# schema1.net
KiCad netlist of a schematic drawn in Altium Designer
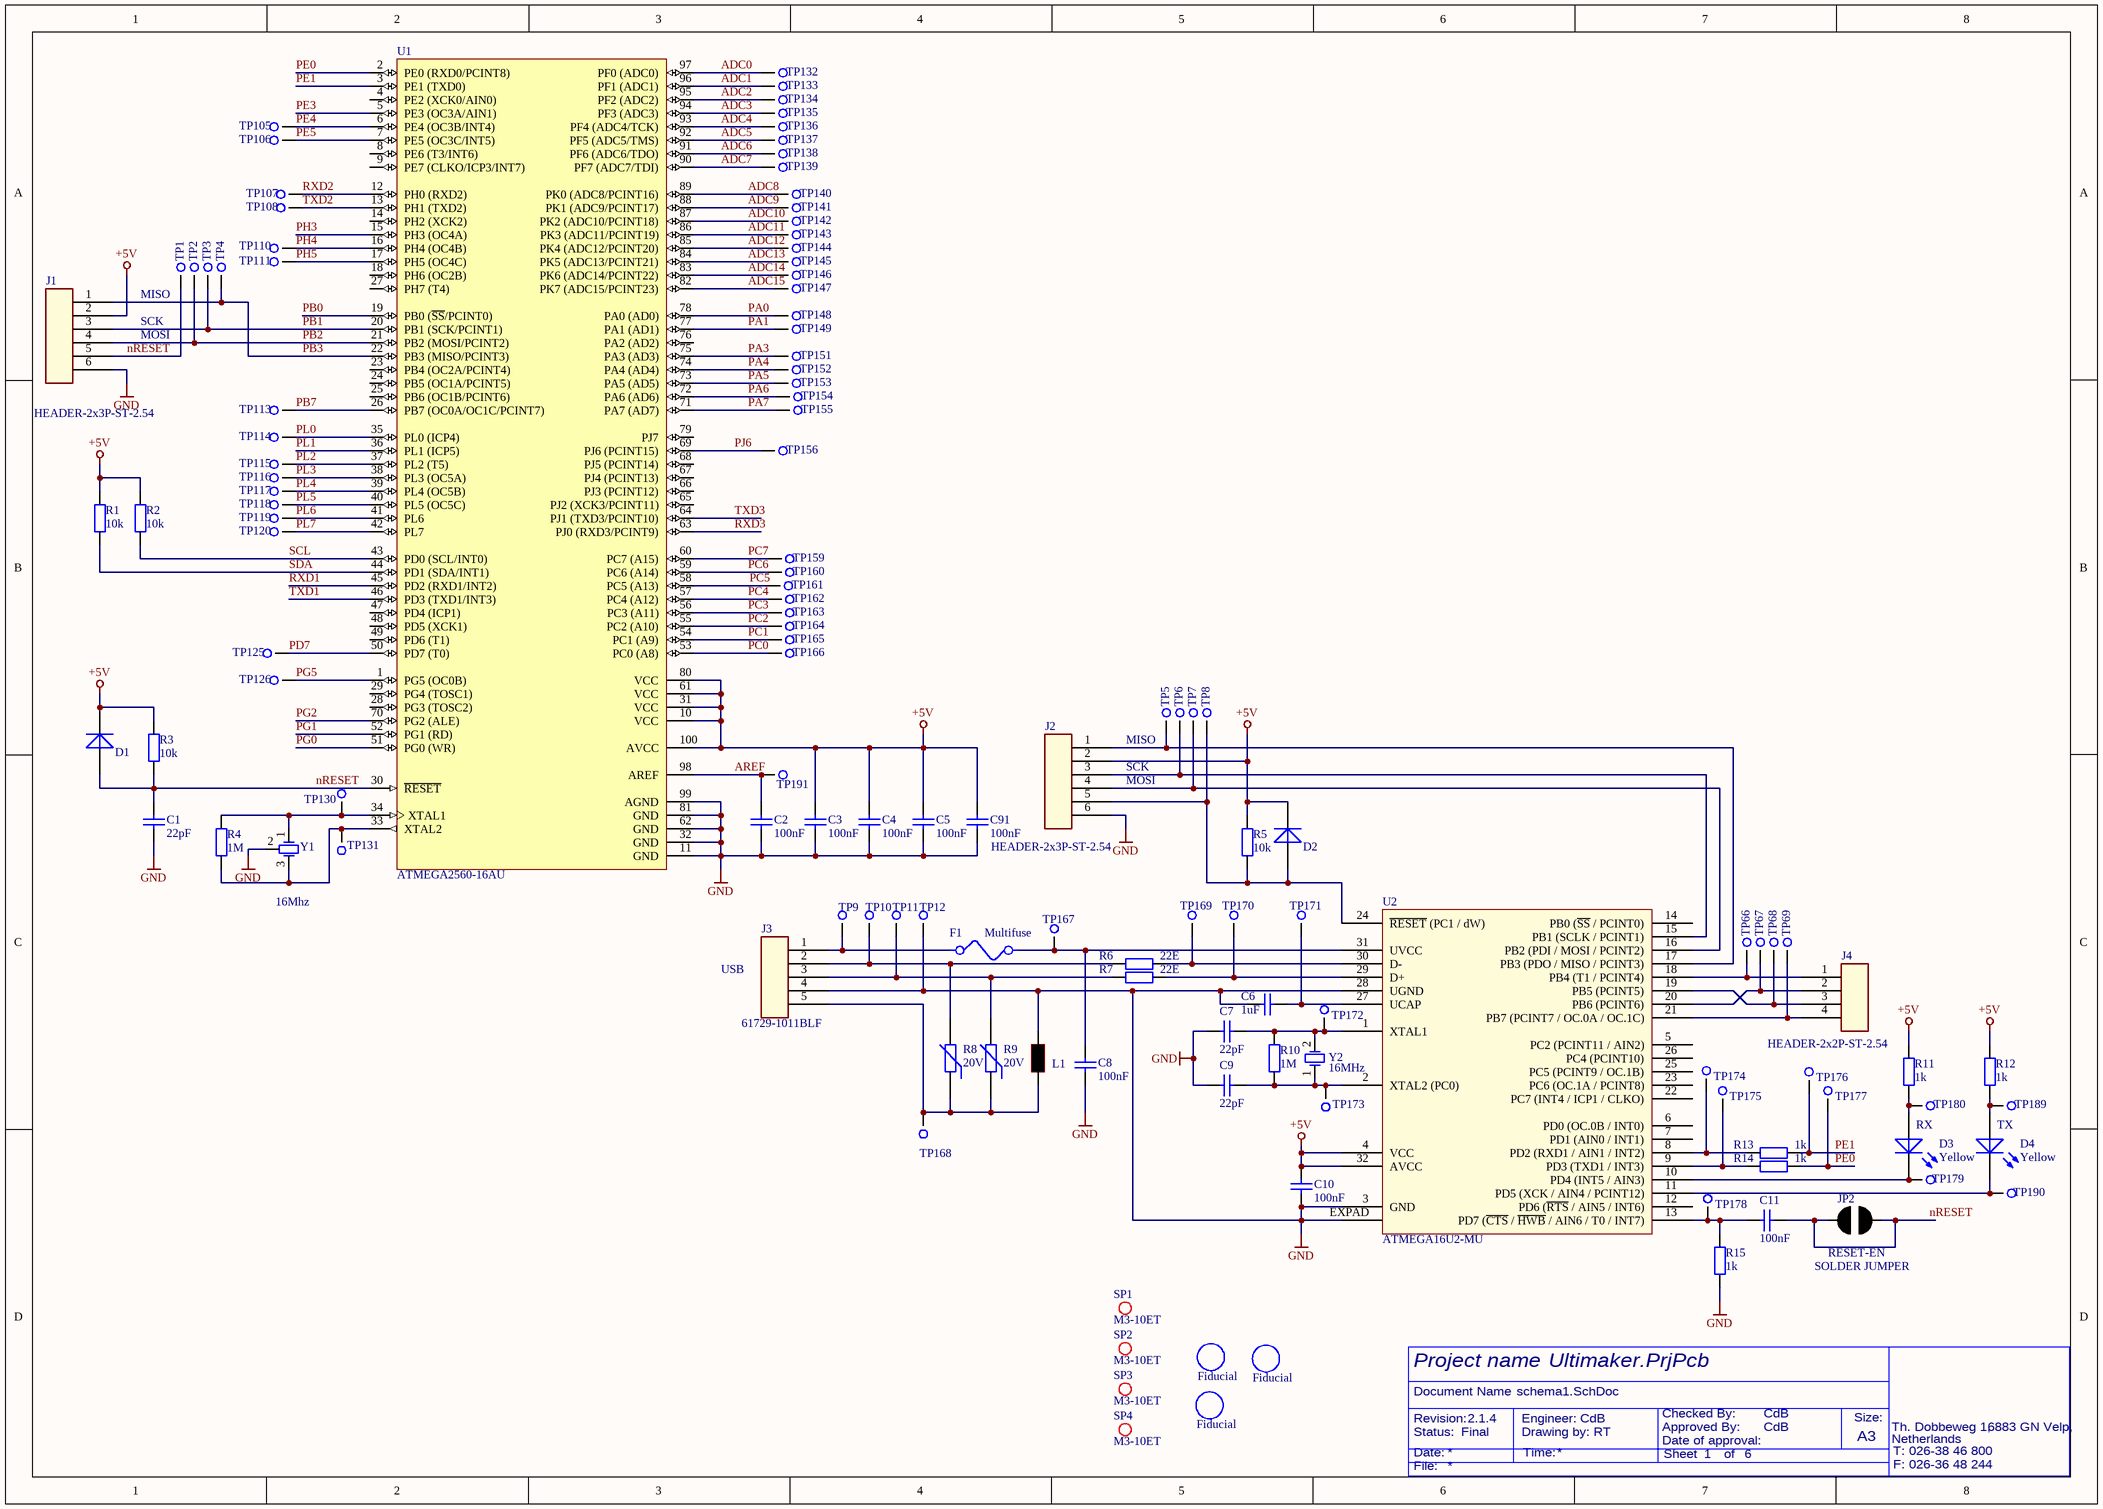
[diagram p0: schema1.SchDoc]

(export (version "E")
  (design (tool "Eeschema 10.0.6"))
  (components
    (comp (ref "C1")
      (value "22pF")
      (footprint "C0603")
      (description "RO C0G 22pF 2% 50V  0603")
      (libsource (lib "Database_Faber") (part "Capacitor"))
    )
    (comp (ref "C2")
      (value "100nF")
      (footprint "C0603")
      (description "RO X7R 100nF 10% 50V 0603")
      (libsource (lib "Database_Faber") (part "Capacitor"))
    )
    (comp (ref "C3")
      (value "100nF")
      (footprint "C0603")
      (description "RO X7R 100nF 10% 50V 0603")
      (libsource (lib "Database_Faber") (part "Capacitor"))
    )
    (comp (ref "C4")
      (value "100nF")
      (footprint "C0603")
      (description "RO X7R 100nF 10% 50V 0603")
      (libsource (lib "Database_Faber") (part "Capacitor"))
    )
    (comp (ref "C5")
      (value "100nF")
      (footprint "C0603")
      (description "RO X7R 100nF 10% 50V 0603")
      (libsource (lib "Database_Faber") (part "Capacitor"))
    )
    (comp (ref "C6")
      (value "1uF")
      (footprint "C0603")
      (description "RO X5R 1uF 10% 10V 0603")
      (libsource (lib "Database_Faber") (part "Capacitor"))
    )
    (comp (ref "C7")
      (value "22pF")
      (footprint "C0603")
      (description "RO C0G 22pF 2% 50V  0603")
      (libsource (lib "Database_Faber") (part "Capacitor"))
    )
    (comp (ref "C8")
      (value "100nF")
      (footprint "C0603")
      (description "RO X7R 100nF 10% 50V 0603")
      (libsource (lib "Database_Faber") (part "Capacitor"))
    )
    (comp (ref "C9")
      (value "22pF")
      (footprint "C0603")
      (description "RO C0G 22pF 2% 50V  0603")
      (libsource (lib "Database_Faber") (part "Capacitor"))
    )
    (comp (ref "C10")
      (value "100nF")
      (footprint "C0603")
      (description "RO X7R 100nF 10% 50V 0603")
      (libsource (lib "Database_Faber") (part "Capacitor"))
    )
    (comp (ref "C11")
      (value "100nF")
      (footprint "C0603")
      (description "RO X7R 100nF 10% 50V 0603")
      (libsource (lib "Database_Faber") (part "Capacitor"))
    )
    (comp (ref "C91")
      (value "100nF")
      (footprint "C0603")
      (description "RO X7R 100nF 10% 50V 0603")
      (libsource (lib "Database_Faber") (part "Capacitor"))
    )
    (comp (ref "D1")
      (value "1N4148")
      (footprint "SOD323")
      (description "RO DIODE 1N4148WS-V-GS08 SOT-323  VISHAY")
      (fields (field (name "MFG") "VISHAY"))
      (libsource (lib "Database_Faber") (part "Diode"))
    )
    (comp (ref "D2")
      (value "1N4148")
      (footprint "SOD323")
      (description "RO DIODE 1N4148WS-V-GS08 SOT-323  VISHAY")
      (fields (field (name "MFG") "VISHAY"))
      (libsource (lib "Database_Faber") (part "Diode"))
    )
    (comp (ref "D3")
      (value "Yellow")
      (footprint "LED0805-YELLOW")
      (description "RO LED GEEL HSMY-C170 0805  AVAGO")
      (fields (field (name "MFG") "AVAGO"))
      (libsource (lib "Database_Faber") (part "LED"))
    )
    (comp (ref "D4")
      (value "Yellow")
      (footprint "LED0805-YELLOW")
      (description "RO LED GEEL HSMY-C170 0805  AVAGO")
      (fields (field (name "MFG") "AVAGO"))
      (libsource (lib "Database_Faber") (part "LED"))
    )
    (comp (ref "F1")
      (value "Multifuse")
      (footprint "Multifuse1812")
      (description "RO ZEK MULTI 500MA SMD 1812 MF-MSMF050-2 BOURNS")
      (fields (field (name "MFG") "BOURNS"))
      (libsource (lib "Database_Faber") (part "Multifuse"))
    )
    (comp (ref "Fid1")
      (value "Fiducial")
      (footprint "Fiducial")
      (libsource (lib "Database_Faber") (part "Fiducial"))
    )
    (comp (ref "Fid2")
      (value "Fiducial")
      (footprint "Fiducial")
      (libsource (lib "Database_Faber") (part "Fiducial"))
    )
    (comp (ref "Fid3")
      (value "Fiducial")
      (footprint "Fiducial")
      (libsource (lib "Database_Faber") (part "Fiducial"))
    )
    (comp (ref "J1")
      (value "HEADER-2x3P-ST-2.54")
      (footprint "HEADER-2x3P-ST-2.54")
      (description "RO CONN PR HDR 2X3P H4B-06DS-0000 INT")
      (libsource (lib "Database_Faber") (part "HEADER 6"))
    )
    (comp (ref "J2")
      (value "HEADER-2x3P-ST-2.54")
      (footprint "HEADER-2x3P-ST-2.54")
      (description "RO CONN PR HDR 2X3P H4B-06DS-0000 INT")
      (libsource (lib "Database_Faber") (part "HEADER 6"))
    )
    (comp (ref "J3")
      (value "61729-1011BLF")
      (footprint "61729-1011BLF")
      (description "RO CONN PR USB-B HKS 61729-1011BLF FCI")
      (fields (field (name "MFG") "FCI"))
      (libsource (lib "Database_Faber") (part "HEADER 5"))
    )
    (comp (ref "J4")
      (value "HEADER-2x2P-ST-2.54")
      (footprint "HEADER-2x2P-ST-2.54")
      (description "HDR 2X2P")
      (libsource (lib "Database_Faber") (part "HEADER 4"))
    )
    (comp (ref "JP2")
      (value "SOLDER JUMPER")
      (footprint "JUMPER 2 SOLDER")
      (libsource (lib "Database_Faber") (part "JUMPER 2 SOLDER"))
    )
    (comp (ref "L1")
      (value "Bead")
      (footprint "L0805")
      (description "RO FERRIET BLM21PG221SN1D  0805")
      (libsource (lib "Database_Faber") (part "Bead"))
    )
    (comp (ref "R1")
      (value "10k")
      (footprint "R0603")
      (description "RO RES 10k0 1% 0,063W  0603")
      (libsource (lib "") (part "Resistor_2"))
    )
    (comp (ref "R2")
      (value "10k")
      (footprint "R0603")
      (description "RO RES 10k0 1% 0,063W  0603")
      (libsource (lib "") (part "Resistor_2"))
    )
    (comp (ref "R3")
      (value "10k")
      (footprint "R0603")
      (description "RO RES 10k0 1% 0,063W  0603")
      (libsource (lib "") (part "Resistor_1"))
    )
    (comp (ref "R4")
      (value "1M")
      (footprint "R0603")
      (description "RO RES 1M0 1% 0,1W 0603")
      (libsource (lib "") (part "Resistor_1"))
    )
    (comp (ref "R5")
      (value "10k")
      (footprint "R0603")
      (description "RO RES 10k0 1% 0,063W  0603")
      (libsource (lib "") (part "Resistor_2"))
    )
    (comp (ref "R6")
      (value "22E")
      (footprint "R0603")
      (description "RO RES 22E0 1% 0,063W 0603")
      (libsource (lib "Database_Faber") (part "Resistor"))
    )
    (comp (ref "R7")
      (value "22E")
      (footprint "R0603")
      (description "RO RES 22E0 1% 0,063W 0603")
      (libsource (lib "Database_Faber") (part "Resistor"))
    )
    (comp (ref "R8")
      (value "20V")
      (footprint "R0603")
      (description "RO VDR 0603 CG0603MLC-05E")
      (fields (field (name "MFG") "BOURNS"))
      (libsource (lib "Database_Faber") (part "Varistor"))
    )
    (comp (ref "R9")
      (value "20V")
      (footprint "R0603")
      (description "RO VDR 0603 CG0603MLC-05E")
      (fields (field (name "MFG") "BOURNS"))
      (libsource (lib "Database_Faber") (part "Varistor"))
    )
    (comp (ref "R10")
      (value "1M")
      (footprint "R0603")
      (description "RO RES 1M0 1% 0,1W 0603")
      (libsource (lib "") (part "Resistor_1"))
    )
    (comp (ref "R11")
      (value "1k")
      (footprint "R0603")
      (description "RO RES 1k0 1% 0,1W  0603")
      (libsource (lib "") (part "Resistor_1"))
    )
    (comp (ref "R12")
      (value "1k")
      (footprint "R0603")
      (description "RO RES 1k0 1% 0,1W  0603")
      (libsource (lib "") (part "Resistor_1"))
    )
    (comp (ref "R13")
      (value "1k")
      (footprint "R0603")
      (description "RO RES 1k0 1% 0,1W  0603")
      (libsource (lib "Database_Faber") (part "Resistor"))
    )
    (comp (ref "R14")
      (value "1k")
      (footprint "R0603")
      (description "RO RES 1k0 1% 0,1W  0603")
      (libsource (lib "Database_Faber") (part "Resistor"))
    )
    (comp (ref "R15")
      (value "1k")
      (footprint "R0603")
      (description "RO RES 1k0 1% 0,1W  0603")
      (libsource (lib "") (part "Resistor_2"))
    )
    (comp (ref "SP1")
      (value "M3-10ET")
      (footprint "Spacer M3-10ET")
      (description "MOER-SMD SMTSO-M3-10ET  PEM")
      (fields (field (name "MFG") "PEM"))
      (libsource (lib "Faber_SCH_lib") (part "Spacer M3-10ET"))
    )
    (comp (ref "SP2")
      (value "M3-10ET")
      (footprint "Spacer M3-10ET")
      (description "Spacer SMTSO-M3-10ET")
      (fields (field (name "MFG") "PEM"))
      (libsource (lib "Faber_SCH_lib") (part "Spacer M3-10ET"))
    )
    (comp (ref "SP3")
      (value "M3-10ET")
      (footprint "Spacer M3-10ET")
      (description "Spacer SMTSO-M3-10ET")
      (fields (field (name "MFG") "PEM"))
      (libsource (lib "Faber_SCH_lib") (part "Spacer M3-10ET"))
    )
    (comp (ref "SP4")
      (value "M3-10ET")
      (footprint "Spacer M3-10ET")
      (description "Spacer SMTSO-M3-10ET")
      (fields (field (name "MFG") "PEM"))
      (libsource (lib "Faber_SCH_lib") (part "Spacer M3-10ET"))
    )
    (comp (ref "TP1")
      (value "Testpoint")
      (footprint "Testpoint")
      (libsource (lib "Database_Faber") (part "Testpoint"))
    )
    (comp (ref "TP2")
      (value "Testpoint")
      (footprint "Testpoint")
      (libsource (lib "Database_Faber") (part "Testpoint"))
    )
    (comp (ref "TP3")
      (value "Testpoint")
      (footprint "Testpoint")
      (libsource (lib "Database_Faber") (part "Testpoint"))
    )
    (comp (ref "TP4")
      (value "Testpoint")
      (footprint "Testpoint")
      (libsource (lib "Database_Faber") (part "Testpoint"))
    )
    (comp (ref "TP5")
      (value "Testpoint")
      (footprint "Testpoint")
      (libsource (lib "Database_Faber") (part "Testpoint"))
    )
    (comp (ref "TP6")
      (value "Testpoint")
      (footprint "Testpoint")
      (libsource (lib "Database_Faber") (part "Testpoint"))
    )
    (comp (ref "TP7")
      (value "Testpoint")
      (footprint "Testpoint")
      (libsource (lib "Database_Faber") (part "Testpoint"))
    )
    (comp (ref "TP8")
      (value "Testpoint")
      (footprint "Testpoint")
      (libsource (lib "Database_Faber") (part "Testpoint"))
    )
    (comp (ref "TP9")
      (value "Testpoint")
      (footprint "Testpoint")
      (libsource (lib "Database_Faber") (part "Testpoint"))
    )
    (comp (ref "TP10")
      (value "Testpoint")
      (footprint "Testpoint")
      (libsource (lib "Database_Faber") (part "Testpoint"))
    )
    (comp (ref "TP11")
      (value "Testpoint")
      (footprint "Testpoint")
      (libsource (lib "Database_Faber") (part "Testpoint"))
    )
    (comp (ref "TP12")
      (value "Testpoint")
      (footprint "Testpoint")
      (libsource (lib "Database_Faber") (part "Testpoint"))
    )
    (comp (ref "TP66")
      (value "Testpoint")
      (footprint "Testpoint")
      (libsource (lib "Database_Faber") (part "Testpoint"))
    )
    (comp (ref "TP67")
      (value "Testpoint")
      (footprint "Testpoint")
      (libsource (lib "Database_Faber") (part "Testpoint"))
    )
    (comp (ref "TP68")
      (value "Testpoint")
      (footprint "Testpoint")
      (libsource (lib "Database_Faber") (part "Testpoint"))
    )
    (comp (ref "TP69")
      (value "Testpoint")
      (footprint "Testpoint")
      (libsource (lib "Database_Faber") (part "Testpoint"))
    )
    (comp (ref "TP105")
      (value "Testpoint 1.6mm")
      (footprint "Testpoint 1.6mm")
      (libsource (lib "Ultimaker") (part "Testpoint 1.6mm"))
    )
    (comp (ref "TP106")
      (value "Testpoint 1.6mm")
      (footprint "Testpoint 1.6mm")
      (libsource (lib "Ultimaker") (part "Testpoint 1.6mm"))
    )
    (comp (ref "TP107")
      (value "Testpoint 1.6mm")
      (footprint "Testpoint 1.6mm")
      (libsource (lib "Ultimaker") (part "Testpoint 1.6mm"))
    )
    (comp (ref "TP108")
      (value "Testpoint 1.6mm")
      (footprint "Testpoint 1.6mm")
      (libsource (lib "Ultimaker") (part "Testpoint 1.6mm"))
    )
    (comp (ref "TP110")
      (value "Testpoint 1.6mm")
      (footprint "Testpoint 1.6mm")
      (libsource (lib "Ultimaker") (part "Testpoint 1.6mm"))
    )
    (comp (ref "TP111")
      (value "Testpoint 1.6mm")
      (footprint "Testpoint 1.6mm")
      (libsource (lib "Ultimaker") (part "Testpoint 1.6mm"))
    )
    (comp (ref "TP113")
      (value "Testpoint 1.6mm")
      (footprint "Testpoint 1.6mm")
      (libsource (lib "Ultimaker") (part "Testpoint 1.6mm"))
    )
    (comp (ref "TP114")
      (value "Testpoint 1.6mm")
      (footprint "Testpoint 1.6mm")
      (libsource (lib "Ultimaker") (part "Testpoint 1.6mm"))
    )
    (comp (ref "TP115")
      (value "Testpoint 1.6mm")
      (footprint "Testpoint 1.6mm")
      (libsource (lib "Ultimaker") (part "Testpoint 1.6mm"))
    )
    (comp (ref "TP116")
      (value "Testpoint 1.6mm")
      (footprint "Testpoint 1.6mm")
      (libsource (lib "Ultimaker") (part "Testpoint 1.6mm"))
    )
    (comp (ref "TP117")
      (value "Testpoint 1.6mm")
      (footprint "Testpoint 1.6mm")
      (libsource (lib "Ultimaker") (part "Testpoint 1.6mm"))
    )
    (comp (ref "TP118")
      (value "Testpoint 1.6mm")
      (footprint "Testpoint 1.6mm")
      (libsource (lib "Ultimaker") (part "Testpoint 1.6mm"))
    )
    (comp (ref "TP119")
      (value "Testpoint 1.6mm")
      (footprint "Testpoint 1.6mm")
      (libsource (lib "Ultimaker") (part "Testpoint 1.6mm"))
    )
    (comp (ref "TP120")
      (value "Testpoint 1.6mm")
      (footprint "Testpoint 1.6mm")
      (libsource (lib "Ultimaker") (part "Testpoint 1.6mm"))
    )
    (comp (ref "TP125")
      (value "Testpoint 1.6mm")
      (footprint "Testpoint 1.6mm")
      (libsource (lib "Ultimaker") (part "Testpoint 1.6mm"))
    )
    (comp (ref "TP126")
      (value "Testpoint 1.6mm")
      (footprint "Testpoint 1.6mm")
      (libsource (lib "Ultimaker") (part "Testpoint 1.6mm"))
    )
    (comp (ref "TP130")
      (value "Testpoint 1.6mm")
      (footprint "Testpoint 1.6mm")
      (libsource (lib "Ultimaker") (part "Testpoint 1.6mm"))
    )
    (comp (ref "TP131")
      (value "Testpoint 1.6mm")
      (footprint "Testpoint 1.6mm")
      (libsource (lib "Ultimaker") (part "Testpoint 1.6mm"))
    )
    (comp (ref "TP132")
      (value "Testpoint 1.6mm")
      (footprint "Testpoint 1.6mm")
      (libsource (lib "Ultimaker") (part "Testpoint 1.6mm"))
    )
    (comp (ref "TP133")
      (value "Testpoint 1.6mm")
      (footprint "Testpoint 1.6mm")
      (libsource (lib "Ultimaker") (part "Testpoint 1.6mm"))
    )
    (comp (ref "TP134")
      (value "Testpoint 1.6mm")
      (footprint "Testpoint 1.6mm")
      (libsource (lib "Ultimaker") (part "Testpoint 1.6mm"))
    )
    (comp (ref "TP135")
      (value "Testpoint 1.6mm")
      (footprint "Testpoint 1.6mm")
      (libsource (lib "Ultimaker") (part "Testpoint 1.6mm"))
    )
    (comp (ref "TP136")
      (value "Testpoint 1.6mm")
      (footprint "Testpoint 1.6mm")
      (libsource (lib "Ultimaker") (part "Testpoint 1.6mm"))
    )
    (comp (ref "TP137")
      (value "Testpoint 1.6mm")
      (footprint "Testpoint 1.6mm")
      (libsource (lib "Ultimaker") (part "Testpoint 1.6mm"))
    )
    (comp (ref "TP138")
      (value "Testpoint 1.6mm")
      (footprint "Testpoint 1.6mm")
      (libsource (lib "Ultimaker") (part "Testpoint 1.6mm"))
    )
    (comp (ref "TP139")
      (value "Testpoint 1.6mm")
      (footprint "Testpoint 1.6mm")
      (libsource (lib "Ultimaker") (part "Testpoint 1.6mm"))
    )
    (comp (ref "TP140")
      (value "Testpoint 1.6mm")
      (footprint "Testpoint 1.6mm")
      (libsource (lib "Ultimaker") (part "Testpoint 1.6mm"))
    )
    (comp (ref "TP141")
      (value "Testpoint 1.6mm")
      (footprint "Testpoint 1.6mm")
      (libsource (lib "Ultimaker") (part "Testpoint 1.6mm"))
    )
    (comp (ref "TP142")
      (value "Testpoint 1.6mm")
      (footprint "Testpoint 1.6mm")
      (libsource (lib "Ultimaker") (part "Testpoint 1.6mm"))
    )
    (comp (ref "TP143")
      (value "Testpoint 1.6mm")
      (footprint "Testpoint 1.6mm")
      (libsource (lib "Ultimaker") (part "Testpoint 1.6mm"))
    )
    (comp (ref "TP144")
      (value "Testpoint 1.6mm")
      (footprint "Testpoint 1.6mm")
      (libsource (lib "Ultimaker") (part "Testpoint 1.6mm"))
    )
    (comp (ref "TP145")
      (value "Testpoint 1.6mm")
      (footprint "Testpoint 1.6mm")
      (libsource (lib "Ultimaker") (part "Testpoint 1.6mm"))
    )
    (comp (ref "TP146")
      (value "Testpoint 1.6mm")
      (footprint "Testpoint 1.6mm")
      (libsource (lib "Ultimaker") (part "Testpoint 1.6mm"))
    )
    (comp (ref "TP147")
      (value "Testpoint 1.6mm")
      (footprint "Testpoint 1.6mm")
      (libsource (lib "Ultimaker") (part "Testpoint 1.6mm"))
    )
    (comp (ref "TP148")
      (value "Testpoint 1.6mm")
      (footprint "Testpoint 1.6mm")
      (libsource (lib "Ultimaker") (part "Testpoint 1.6mm"))
    )
    (comp (ref "TP149")
      (value "Testpoint 1.6mm")
      (footprint "Testpoint 1.6mm")
      (libsource (lib "Ultimaker") (part "Testpoint 1.6mm"))
    )
    (comp (ref "TP151")
      (value "Testpoint 1.6mm")
      (footprint "Testpoint 1.6mm")
      (libsource (lib "Ultimaker") (part "Testpoint 1.6mm"))
    )
    (comp (ref "TP152")
      (value "Testpoint 1.6mm")
      (footprint "Testpoint 1.6mm")
      (libsource (lib "Ultimaker") (part "Testpoint 1.6mm"))
    )
    (comp (ref "TP153")
      (value "Testpoint 1.6mm")
      (footprint "Testpoint 1.6mm")
      (libsource (lib "Ultimaker") (part "Testpoint 1.6mm"))
    )
    (comp (ref "TP154")
      (value "Testpoint 1.6mm")
      (footprint "Testpoint 1.6mm")
      (libsource (lib "Ultimaker") (part "Testpoint 1.6mm"))
    )
    (comp (ref "TP155")
      (value "Testpoint 1.6mm")
      (footprint "Testpoint 1.6mm")
      (libsource (lib "Ultimaker") (part "Testpoint 1.6mm"))
    )
    (comp (ref "TP156")
      (value "Testpoint 1.6mm")
      (footprint "Testpoint 1.6mm")
      (libsource (lib "Ultimaker") (part "Testpoint 1.6mm"))
    )
    (comp (ref "TP159")
      (value "Testpoint 1.6mm")
      (footprint "Testpoint 1.6mm")
      (libsource (lib "Ultimaker") (part "Testpoint 1.6mm"))
    )
    (comp (ref "TP160")
      (value "Testpoint 1.6mm")
      (footprint "Testpoint 1.6mm")
      (libsource (lib "Ultimaker") (part "Testpoint 1.6mm"))
    )
    (comp (ref "TP161")
      (value "Testpoint 1.6mm")
      (footprint "Testpoint 1.6mm")
      (libsource (lib "Ultimaker") (part "Testpoint 1.6mm"))
    )
    (comp (ref "TP162")
      (value "Testpoint 1.6mm")
      (footprint "Testpoint 1.6mm")
      (libsource (lib "Ultimaker") (part "Testpoint 1.6mm"))
    )
    (comp (ref "TP163")
      (value "Testpoint 1.6mm")
      (footprint "Testpoint 1.6mm")
      (libsource (lib "Ultimaker") (part "Testpoint 1.6mm"))
    )
    (comp (ref "TP164")
      (value "Testpoint 1.6mm")
      (footprint "Testpoint 1.6mm")
      (libsource (lib "Ultimaker") (part "Testpoint 1.6mm"))
    )
    (comp (ref "TP165")
      (value "Testpoint 1.6mm")
      (footprint "Testpoint 1.6mm")
      (libsource (lib "Ultimaker") (part "Testpoint 1.6mm"))
    )
    (comp (ref "TP166")
      (value "Testpoint 1.6mm")
      (footprint "Testpoint 1.6mm")
      (libsource (lib "Ultimaker") (part "Testpoint 1.6mm"))
    )
    (comp (ref "TP167")
      (value "Testpoint 1.6mm")
      (footprint "Testpoint 1.6mm")
      (libsource (lib "Ultimaker") (part "Testpoint 1.6mm"))
    )
    (comp (ref "TP168")
      (value "Testpoint 1.6mm")
      (footprint "Testpoint 1.6mm")
      (libsource (lib "Ultimaker") (part "Testpoint 1.6mm"))
    )
    (comp (ref "TP169")
      (value "Testpoint 1.6mm")
      (footprint "Testpoint 1.6mm")
      (libsource (lib "Ultimaker") (part "Testpoint 1.6mm"))
    )
    (comp (ref "TP170")
      (value "Testpoint 1.6mm")
      (footprint "Testpoint 1.6mm")
      (libsource (lib "Ultimaker") (part "Testpoint 1.6mm"))
    )
    (comp (ref "TP171")
      (value "Testpoint 1.6mm")
      (footprint "Testpoint 1.6mm")
      (libsource (lib "Ultimaker") (part "Testpoint 1.6mm"))
    )
    (comp (ref "TP172")
      (value "Testpoint 1.6mm")
      (footprint "Testpoint 1.6mm")
      (libsource (lib "Ultimaker") (part "Testpoint 1.6mm"))
    )
    (comp (ref "TP173")
      (value "Testpoint 1.6mm")
      (footprint "Testpoint 1.6mm")
      (libsource (lib "Ultimaker") (part "Testpoint 1.6mm"))
    )
    (comp (ref "TP174")
      (value "Testpoint 1.6mm")
      (footprint "Testpoint 1.6mm")
      (libsource (lib "Ultimaker") (part "Testpoint 1.6mm"))
    )
    (comp (ref "TP175")
      (value "Testpoint 1.6mm")
      (footprint "Testpoint 1.6mm")
      (libsource (lib "Ultimaker") (part "Testpoint 1.6mm"))
    )
    (comp (ref "TP176")
      (value "Testpoint 1.6mm")
      (footprint "Testpoint 1.6mm")
      (libsource (lib "Ultimaker") (part "Testpoint 1.6mm"))
    )
    (comp (ref "TP177")
      (value "Testpoint 1.6mm")
      (footprint "Testpoint 1.6mm")
      (libsource (lib "Ultimaker") (part "Testpoint 1.6mm"))
    )
    (comp (ref "TP178")
      (value "Testpoint 1.6mm")
      (footprint "Testpoint 1.6mm")
      (libsource (lib "Ultimaker") (part "Testpoint 1.6mm"))
    )
    (comp (ref "TP179")
      (value "Testpoint 1.6mm")
      (footprint "Testpoint 1.6mm")
      (libsource (lib "Ultimaker") (part "Testpoint 1.6mm"))
    )
    (comp (ref "TP180")
      (value "Testpoint 1.6mm")
      (footprint "Testpoint 1.6mm")
      (libsource (lib "Ultimaker") (part "Testpoint 1.6mm"))
    )
    (comp (ref "TP189")
      (value "Testpoint 1.6mm")
      (footprint "Testpoint 1.6mm")
      (libsource (lib "Ultimaker") (part "Testpoint 1.6mm"))
    )
    (comp (ref "TP190")
      (value "Testpoint 1.6mm")
      (footprint "Testpoint 1.6mm")
      (libsource (lib "Ultimaker") (part "Testpoint 1.6mm"))
    )
    (comp (ref "TP191")
      (value "Testpoint 1.6mm")
      (footprint "Testpoint 1.6mm")
      (libsource (lib "Ultimaker") (part "Testpoint 1.6mm"))
    )
    (comp (ref "U1")
      (value "ATMEGA2560-16AU")
      (footprint "TSQFP50P1600X1600X120-100N")
      (description "RO IC ATMEGA2560-16AU TQFP-100 ATMEL")
      (fields (field (name "MFG") "Atmel"))
      (libsource (lib "Database_Faber") (part "ATmega2560-16AU"))
    )
    (comp (ref "U2")
      (value "ATMEGA16U2-MU")
      (footprint "QFN50P500X500X100-32-EX")
      (description "RO IC ATMEGA16U2-MU QFN-32 ATMEL")
      (fields (field (name "MFG") "Atmel"))
      (libsource (lib "Database_Faber") (part "ATMEGA16U2-MU"))
    )
    (comp (ref "Y1")
      (value "16Mhz")
      (footprint "CSTC")
      (description "RO KRIS 16MHz CSTCE16M0V53-R0 SMD MURATA")
      (fields (field (name "MFG") "MURATA"))
      (libsource (lib "Database_Faber") (part "XTAL-3"))
    )
    (comp (ref "Y2")
      (value "16MHz")
      (footprint "XT49M-2016M")
      (description "RO KRISTAL 16.0MHz  HC49/4HSMX  SMD CMAC")
      (fields (field (name "MFG") "CMAC"))
      (libsource (lib "Database_Faber") (part "XTAL-2"))
    )
  )
  (nets
    (net (code "1") (name "+5V") (class "Default")
      (node (ref "C10") (pin "2") (pinfunction "2_2") (pintype "passive"))
      (node (ref "C3") (pin "2") (pinfunction "2_2") (pintype "passive"))
      (node (ref "C4") (pin "2") (pinfunction "2_2") (pintype "passive"))
      (node (ref "C5") (pin "2") (pinfunction "2_2") (pintype "passive"))
      (node (ref "C91") (pin "2") (pinfunction "2_2") (pintype "passive"))
      (node (ref "D1") (pin "2") (pinfunction "K_2") (pintype "passive"))
      (node (ref "D2") (pin "2") (pinfunction "K_2") (pintype "passive"))
      (node (ref "J1") (pin "2") (pinfunction "2_2") (pintype "passive"))
      (node (ref "J2") (pin "2") (pinfunction "2_2") (pintype "passive"))
      (node (ref "R1") (pin "1") (pinfunction "1_1") (pintype "passive"))
      (node (ref "R11") (pin "2") (pinfunction "2_2") (pintype "passive"))
      (node (ref "R12") (pin "2") (pinfunction "2_2") (pintype "passive"))
      (node (ref "R2") (pin "1") (pinfunction "1_1") (pintype "passive"))
      (node (ref "R3") (pin "2") (pinfunction "2_2") (pintype "passive"))
      (node (ref "R5") (pin "1") (pinfunction "1_1") (pintype "passive"))
      (node (ref "U1") (pin "10") (pinfunction "VCC_10") (pintype "power_in"))
      (node (ref "U1") (pin "100") (pinfunction "AVCC_100") (pintype "power_in"))
      (node (ref "U1") (pin "31") (pinfunction "VCC_31") (pintype "power_in"))
      (node (ref "U1") (pin "61") (pinfunction "VCC_61") (pintype "power_in"))
      (node (ref "U1") (pin "80") (pinfunction "VCC_80") (pintype "power_in"))
      (node (ref "U2") (pin "32") (pinfunction "AVCC_32") (pintype "passive"))
      (node (ref "U2") (pin "4") (pinfunction "VCC_4") (pintype "passive"))
    )
    (net (code "2") (name "/ADC0") (class "Default")
      (node (ref "TP132") (pin "1") (pinfunction "1_1") (pintype "passive"))
      (node (ref "U1") (pin "97") (pinfunction "PF0_(ADC0)_97") (pintype "bidirectional"))
    )
    (net (code "3") (name "/ADC1") (class "Default")
      (node (ref "TP133") (pin "1") (pinfunction "1_1") (pintype "passive"))
      (node (ref "U1") (pin "96") (pinfunction "PF1_(ADC1)_96") (pintype "bidirectional"))
    )
    (net (code "4") (name "/ADC2") (class "Default")
      (node (ref "TP134") (pin "1") (pinfunction "1_1") (pintype "passive"))
      (node (ref "U1") (pin "95") (pinfunction "PF2_(ADC2)_95") (pintype "bidirectional"))
    )
    (net (code "5") (name "/ADC3") (class "Default")
      (node (ref "TP135") (pin "1") (pinfunction "1_1") (pintype "passive"))
      (node (ref "U1") (pin "94") (pinfunction "PF3_(ADC3)_94") (pintype "bidirectional"))
    )
    (net (code "6") (name "/ADC4") (class "Default")
      (node (ref "TP136") (pin "1") (pinfunction "1_1") (pintype "passive"))
      (node (ref "U1") (pin "93") (pinfunction "PF4_(ADC4/TCK)_93") (pintype "bidirectional"))
    )
    (net (code "7") (name "/ADC5") (class "Default")
      (node (ref "TP137") (pin "1") (pinfunction "1_1") (pintype "passive"))
      (node (ref "U1") (pin "92") (pinfunction "PF5_(ADC5/TMS)_92") (pintype "bidirectional"))
    )
    (net (code "8") (name "/ADC6") (class "Default")
      (node (ref "TP138") (pin "1") (pinfunction "1_1") (pintype "passive"))
      (node (ref "U1") (pin "91") (pinfunction "PF6_(ADC6/TDO)_91") (pintype "bidirectional"))
    )
    (net (code "9") (name "/ADC7") (class "Default")
      (node (ref "TP139") (pin "1") (pinfunction "1_1") (pintype "passive"))
      (node (ref "U1") (pin "90") (pinfunction "PF7_(ADC7/TDI)_90") (pintype "bidirectional"))
    )
    (net (code "10") (name "/ADC8") (class "Default")
      (node (ref "TP140") (pin "1") (pinfunction "1_1") (pintype "passive"))
      (node (ref "U1") (pin "89") (pinfunction "PK0_(ADC8/PCINT16)_89") (pintype "bidirectional"))
    )
    (net (code "11") (name "/ADC9") (class "Default")
      (node (ref "TP141") (pin "1") (pinfunction "1_1") (pintype "passive"))
      (node (ref "U1") (pin "88") (pinfunction "PK1_(ADC9/PCINT17)_88") (pintype "bidirectional"))
    )
    (net (code "12") (name "/ADC10") (class "Default")
      (node (ref "TP142") (pin "1") (pinfunction "1_1") (pintype "passive"))
      (node (ref "U1") (pin "87") (pinfunction "PK2_(ADC10/PCINT18)_87") (pintype "bidirectional"))
    )
    (net (code "13") (name "/ADC11") (class "Default")
      (node (ref "TP143") (pin "1") (pinfunction "1_1") (pintype "passive"))
      (node (ref "U1") (pin "86") (pinfunction "PK3_(ADC11/PCINT19)_86") (pintype "bidirectional"))
    )
    (net (code "14") (name "/ADC12") (class "Default")
      (node (ref "TP144") (pin "1") (pinfunction "1_1") (pintype "passive"))
      (node (ref "U1") (pin "85") (pinfunction "PK4_(ADC12/PCINT20)_85") (pintype "bidirectional"))
    )
    (net (code "15") (name "/ADC13") (class "Default")
      (node (ref "TP145") (pin "1") (pinfunction "1_1") (pintype "passive"))
      (node (ref "U1") (pin "84") (pinfunction "PK5_(ADC13/PCINT21)_84") (pintype "bidirectional"))
    )
    (net (code "16") (name "/ADC14") (class "Default")
      (node (ref "TP146") (pin "1") (pinfunction "1_1") (pintype "passive"))
      (node (ref "U1") (pin "83") (pinfunction "PK6_(ADC14/PCINT22)_83") (pintype "bidirectional"))
    )
    (net (code "17") (name "/ADC15") (class "Default")
      (node (ref "TP147") (pin "1") (pinfunction "1_1") (pintype "passive"))
      (node (ref "U1") (pin "82") (pinfunction "PK7_(ADC15/PCINT23)_82") (pintype "bidirectional"))
    )
    (net (code "18") (name "/AREF") (class "Default")
      (node (ref "C2") (pin "2") (pinfunction "2_2") (pintype "passive"))
      (node (ref "TP191") (pin "1") (pinfunction "1_1") (pintype "passive"))
      (node (ref "U1") (pin "98") (pinfunction "AREF_98") (pintype "power_in"))
    )
    (net (code "19") (name "/PA0") (class "Default")
      (node (ref "TP148") (pin "1") (pinfunction "1_1") (pintype "passive"))
      (node (ref "U1") (pin "78") (pinfunction "PA0_(AD0)_78") (pintype "bidirectional"))
    )
    (net (code "20") (name "/PA1") (class "Default")
      (node (ref "TP149") (pin "1") (pinfunction "1_1") (pintype "passive"))
      (node (ref "U1") (pin "77") (pinfunction "PA1_(AD1)_77") (pintype "bidirectional"))
    )
    (net (code "21") (name "/PA3") (class "Default")
      (node (ref "TP151") (pin "1") (pinfunction "1_1") (pintype "passive"))
      (node (ref "U1") (pin "75") (pinfunction "PA3_(AD3)_75") (pintype "bidirectional"))
    )
    (net (code "22") (name "/PA4") (class "Default")
      (node (ref "TP152") (pin "1") (pinfunction "1_1") (pintype "passive"))
      (node (ref "U1") (pin "74") (pinfunction "PA4_(AD4)_74") (pintype "bidirectional"))
    )
    (net (code "23") (name "/PA5") (class "Default")
      (node (ref "TP153") (pin "1") (pinfunction "1_1") (pintype "passive"))
      (node (ref "U1") (pin "73") (pinfunction "PA5_(AD5)_73") (pintype "bidirectional"))
    )
    (net (code "24") (name "/PA6") (class "Default")
      (node (ref "TP154") (pin "1") (pinfunction "1_1") (pintype "passive"))
      (node (ref "U1") (pin "72") (pinfunction "PA6_(AD6)_72") (pintype "bidirectional"))
    )
    (net (code "25") (name "/PA7") (class "Default")
      (node (ref "TP155") (pin "1") (pinfunction "1_1") (pintype "passive"))
      (node (ref "U1") (pin "71") (pinfunction "PA7_(AD7)_71") (pintype "bidirectional"))
    )
    (net (code "26") (name "/PB0") (class "Default")
      (node (ref "U1") (pin "19") (pinfunction "PB0_(~{SS}/PCINT0)_19") (pintype "bidirectional"))
    )
    (net (code "27") (name "/PB1") (class "Default")
      (node (ref "J1") (pin "3") (pinfunction "3_3") (pintype "passive"))
      (node (ref "TP3") (pin "1") (pinfunction "1_1") (pintype "passive"))
      (node (ref "U1") (pin "20") (pinfunction "PB1_(SCK/PCINT1)_20") (pintype "bidirectional"))
    )
    (net (code "28") (name "/PB2") (class "Default")
      (node (ref "J1") (pin "4") (pinfunction "4_4") (pintype "passive"))
      (node (ref "TP2") (pin "1") (pinfunction "1_1") (pintype "passive"))
      (node (ref "U1") (pin "21") (pinfunction "PB2_(MOSI/PCINT2)_21") (pintype "bidirectional"))
    )
    (net (code "29") (name "/PB3") (class "Default")
      (node (ref "J1") (pin "1") (pinfunction "1_1") (pintype "passive"))
      (node (ref "TP4") (pin "1") (pinfunction "1_1") (pintype "passive"))
      (node (ref "U1") (pin "22") (pinfunction "PB3_(MISO/PCINT3)_22") (pintype "bidirectional"))
    )
    (net (code "30") (name "/PB7") (class "Default")
      (node (ref "TP113") (pin "1") (pinfunction "1_1") (pintype "passive"))
      (node (ref "U1") (pin "26") (pinfunction "PB7_(OC0A/OC1C/PCINT7)_26") (pintype "bidirectional"))
    )
    (net (code "31") (name "/PC0") (class "Default")
      (node (ref "TP166") (pin "1") (pinfunction "1_1") (pintype "passive"))
      (node (ref "U1") (pin "53") (pinfunction "PC0_(A8)_53") (pintype "bidirectional"))
    )
    (net (code "32") (name "/PC1") (class "Default")
      (node (ref "TP165") (pin "1") (pinfunction "1_1") (pintype "passive"))
      (node (ref "U1") (pin "54") (pinfunction "PC1_(A9)_54") (pintype "bidirectional"))
    )
    (net (code "33") (name "/PC2") (class "Default")
      (node (ref "TP164") (pin "1") (pinfunction "1_1") (pintype "passive"))
      (node (ref "U1") (pin "55") (pinfunction "PC2_(A10)_55") (pintype "bidirectional"))
    )
    (net (code "34") (name "/PC3") (class "Default")
      (node (ref "TP163") (pin "1") (pinfunction "1_1") (pintype "passive"))
      (node (ref "U1") (pin "56") (pinfunction "PC3_(A11)_56") (pintype "bidirectional"))
    )
    (net (code "35") (name "/PC4") (class "Default")
      (node (ref "TP162") (pin "1") (pinfunction "1_1") (pintype "passive"))
      (node (ref "U1") (pin "57") (pinfunction "PC4_(A12)_57") (pintype "bidirectional"))
    )
    (net (code "36") (name "/PC5") (class "Default")
      (node (ref "TP161") (pin "1") (pinfunction "1_1") (pintype "passive"))
      (node (ref "U1") (pin "58") (pinfunction "PC5_(A13)_58") (pintype "bidirectional"))
    )
    (net (code "37") (name "/PC6") (class "Default")
      (node (ref "TP160") (pin "1") (pinfunction "1_1") (pintype "passive"))
      (node (ref "U1") (pin "59") (pinfunction "PC6_(A14)_59") (pintype "bidirectional"))
    )
    (net (code "38") (name "/PC7") (class "Default")
      (node (ref "TP159") (pin "1") (pinfunction "1_1") (pintype "passive"))
      (node (ref "U1") (pin "60") (pinfunction "PC7_(A15)_60") (pintype "bidirectional"))
    )
    (net (code "39") (name "/PD7") (class "Default")
      (node (ref "TP125") (pin "1") (pinfunction "1_1") (pintype "passive"))
      (node (ref "U1") (pin "50") (pinfunction "PD7_(T0)_50") (pintype "bidirectional"))
    )
    (net (code "40") (name "/PE0") (class "Default")
      (node (ref "R14") (pin "2") (pinfunction "2_2") (pintype "passive"))
      (node (ref "TP177") (pin "1") (pinfunction "1_1") (pintype "passive"))
      (node (ref "U1") (pin "2") (pinfunction "PE0_(RXD0/PCINT8)_2") (pintype "bidirectional"))
    )
    (net (code "41") (name "/PE1") (class "Default")
      (node (ref "R13") (pin "2") (pinfunction "2_2") (pintype "passive"))
      (node (ref "TP176") (pin "1") (pinfunction "1_1") (pintype "passive"))
      (node (ref "U1") (pin "3") (pinfunction "PE1_(TXD0)_3") (pintype "bidirectional"))
    )
    (net (code "42") (name "/PE3") (class "Default")
      (node (ref "U1") (pin "5") (pinfunction "PE3_(OC3A/AIN1)_5") (pintype "bidirectional"))
    )
    (net (code "43") (name "/PE4") (class "Default")
      (node (ref "TP105") (pin "1") (pinfunction "1_1") (pintype "passive"))
      (node (ref "U1") (pin "6") (pinfunction "PE4_(OC3B/INT4)_6") (pintype "bidirectional"))
    )
    (net (code "44") (name "/PE5") (class "Default")
      (node (ref "TP106") (pin "1") (pinfunction "1_1") (pintype "passive"))
      (node (ref "U1") (pin "7") (pinfunction "PE5_(OC3C/INT5)_7") (pintype "bidirectional"))
    )
    (net (code "45") (name "/PG0") (class "Default")
      (node (ref "U1") (pin "51") (pinfunction "PG0_(WR)_51") (pintype "bidirectional"))
    )
    (net (code "46") (name "/PG1") (class "Default")
      (node (ref "U1") (pin "52") (pinfunction "PG1_(RD)_52") (pintype "bidirectional"))
    )
    (net (code "47") (name "/PG2") (class "Default")
      (node (ref "U1") (pin "70") (pinfunction "PG2_(ALE)_70") (pintype "bidirectional"))
    )
    (net (code "48") (name "/PG5") (class "Default")
      (node (ref "TP126") (pin "1") (pinfunction "1_1") (pintype "passive"))
      (node (ref "U1") (pin "1") (pinfunction "PG5_(OC0B)_1") (pintype "bidirectional"))
    )
    (net (code "49") (name "/PH3") (class "Default")
      (node (ref "U1") (pin "15") (pinfunction "PH3_(OC4A)_15") (pintype "bidirectional"))
    )
    (net (code "50") (name "/PH4") (class "Default")
      (node (ref "TP110") (pin "1") (pinfunction "1_1") (pintype "passive"))
      (node (ref "U1") (pin "16") (pinfunction "PH4_(OC4B)_16") (pintype "bidirectional"))
    )
    (net (code "51") (name "/PH5") (class "Default")
      (node (ref "TP111") (pin "1") (pinfunction "1_1") (pintype "passive"))
      (node (ref "U1") (pin "17") (pinfunction "PH5_(OC4C)_17") (pintype "bidirectional"))
    )
    (net (code "52") (name "/PJ6") (class "Default")
      (node (ref "TP156") (pin "1") (pinfunction "1_1") (pintype "passive"))
      (node (ref "U1") (pin "69") (pinfunction "PJ6_(PCINT15)_69") (pintype "bidirectional"))
    )
    (net (code "53") (name "/PL0") (class "Default")
      (node (ref "TP114") (pin "1") (pinfunction "1_1") (pintype "passive"))
      (node (ref "U1") (pin "35") (pinfunction "PL0_(ICP4)_35") (pintype "bidirectional"))
    )
    (net (code "54") (name "/PL1") (class "Default")
      (node (ref "U1") (pin "36") (pinfunction "PL1_(ICP5)_36") (pintype "bidirectional"))
    )
    (net (code "55") (name "/PL2") (class "Default")
      (node (ref "TP115") (pin "1") (pinfunction "1_1") (pintype "passive"))
      (node (ref "U1") (pin "37") (pinfunction "PL2_(T5)_37") (pintype "bidirectional"))
    )
    (net (code "56") (name "/PL3") (class "Default")
      (node (ref "TP116") (pin "1") (pinfunction "1_1") (pintype "passive"))
      (node (ref "U1") (pin "38") (pinfunction "PL3_(OC5A)_38") (pintype "bidirectional"))
    )
    (net (code "57") (name "/PL4") (class "Default")
      (node (ref "TP117") (pin "1") (pinfunction "1_1") (pintype "passive"))
      (node (ref "U1") (pin "39") (pinfunction "PL4_(OC5B)_39") (pintype "bidirectional"))
    )
    (net (code "58") (name "/PL5") (class "Default")
      (node (ref "TP118") (pin "1") (pinfunction "1_1") (pintype "passive"))
      (node (ref "U1") (pin "40") (pinfunction "PL5_(OC5C)_40") (pintype "bidirectional"))
    )
    (net (code "59") (name "/PL6") (class "Default")
      (node (ref "TP119") (pin "1") (pinfunction "1_1") (pintype "passive"))
      (node (ref "U1") (pin "41") (pinfunction "PL6_41") (pintype "bidirectional"))
    )
    (net (code "60") (name "/PL7") (class "Default")
      (node (ref "TP120") (pin "1") (pinfunction "1_1") (pintype "passive"))
      (node (ref "U1") (pin "42") (pinfunction "PL7_42") (pintype "bidirectional"))
    )
    (net (code "61") (name "/RXD1") (class "Default")
      (node (ref "U1") (pin "45") (pinfunction "PD2_(RXD1/INT2)_45") (pintype "bidirectional"))
    )
    (net (code "62") (name "/RXD2") (class "Default")
      (node (ref "TP107") (pin "1") (pinfunction "1_1") (pintype "passive"))
      (node (ref "U1") (pin "12") (pinfunction "PH0_(RXD2)_12") (pintype "bidirectional"))
    )
    (net (code "63") (name "/RXD3") (class "Default")
      (node (ref "U1") (pin "63") (pinfunction "PJ0_(RXD3/PCINT9)_63") (pintype "bidirectional"))
    )
    (net (code "64") (name "/SCL") (class "Default")
      (node (ref "R2") (pin "2") (pinfunction "2_2") (pintype "passive"))
      (node (ref "U1") (pin "43") (pinfunction "PD0_(SCL/INT0)_43") (pintype "bidirectional"))
    )
    (net (code "65") (name "/SDA") (class "Default")
      (node (ref "R1") (pin "2") (pinfunction "2_2") (pintype "passive"))
      (node (ref "U1") (pin "44") (pinfunction "PD1_(SDA/INT1)_44") (pintype "bidirectional"))
    )
    (net (code "66") (name "/TXD1") (class "Default")
      (node (ref "U1") (pin "46") (pinfunction "PD3_(TXD1/INT3)_46") (pintype "bidirectional"))
    )
    (net (code "67") (name "/TXD2") (class "Default")
      (node (ref "TP108") (pin "1") (pinfunction "1_1") (pintype "passive"))
      (node (ref "U1") (pin "13") (pinfunction "PH1_(TXD2)_13") (pintype "bidirectional"))
    )
    (net (code "68") (name "/TXD3") (class "Default")
      (node (ref "U1") (pin "64") (pinfunction "PJ1_(TXD3/PCINT10)_64") (pintype "bidirectional"))
    )
    (net (code "69") (name "/nRESET") (class "Default")
      (node (ref "C1") (pin "2") (pinfunction "2_2") (pintype "passive"))
      (node (ref "C11") (pin "1") (pinfunction "1_1") (pintype "passive"))
      (node (ref "D1") (pin "1") (pinfunction "A_1") (pintype "passive"))
      (node (ref "J1") (pin "5") (pinfunction "5_5") (pintype "passive"))
      (node (ref "JP2") (pin "1") (pinfunction "1_1") (pintype "passive"))
      (node (ref "JP2") (pin "2") (pinfunction "2_2") (pintype "passive"))
      (node (ref "R3") (pin "1") (pinfunction "1_1") (pintype "passive"))
      (node (ref "TP1") (pin "1") (pinfunction "1_1") (pintype "passive"))
      (node (ref "U1") (pin "30") (pinfunction "~{RESET}_30") (pintype "input"))
    )
    (net (code "70") (name "GND") (class "Default")
      (node (ref "C1") (pin "1") (pinfunction "1_1") (pintype "passive"))
      (node (ref "C10") (pin "1") (pinfunction "1_1") (pintype "passive"))
      (node (ref "C2") (pin "1") (pinfunction "1_1") (pintype "passive"))
      (node (ref "C3") (pin "1") (pinfunction "1_1") (pintype "passive"))
      (node (ref "C4") (pin "1") (pinfunction "1_1") (pintype "passive"))
      (node (ref "C5") (pin "1") (pinfunction "1_1") (pintype "passive"))
      (node (ref "C6") (pin "1") (pinfunction "1_1") (pintype "passive"))
      (node (ref "C7") (pin "1") (pinfunction "1_1") (pintype "passive"))
      (node (ref "C8") (pin "1") (pinfunction "1_1") (pintype "passive"))
      (node (ref "C9") (pin "1") (pinfunction "1_1") (pintype "passive"))
      (node (ref "C91") (pin "1") (pinfunction "1_1") (pintype "passive"))
      (node (ref "J1") (pin "6") (pinfunction "6_6") (pintype "passive"))
      (node (ref "J2") (pin "6") (pinfunction "6_6") (pintype "passive"))
      (node (ref "J3") (pin "4") (pinfunction "4_4") (pintype "passive"))
      (node (ref "L1") (pin "1") (pinfunction "1_1") (pintype "passive"))
      (node (ref "R15") (pin "2") (pinfunction "2_2") (pintype "passive"))
      (node (ref "TP12") (pin "1") (pinfunction "1_1") (pintype "passive"))
      (node (ref "U1") (pin "11") (pinfunction "GND_11") (pintype "power_in"))
      (node (ref "U1") (pin "32") (pinfunction "GND_32") (pintype "power_in"))
      (node (ref "U1") (pin "62") (pinfunction "GND_62") (pintype "power_in"))
      (node (ref "U1") (pin "81") (pinfunction "GND_81") (pintype "power_in"))
      (node (ref "U1") (pin "99") (pinfunction "AGND_99") (pintype "power_in"))
      (node (ref "U2") (pin "28") (pinfunction "UGND_28") (pintype "passive"))
      (node (ref "U2") (pin "3") (pinfunction "GND_3") (pintype "passive"))
      (node (ref "U2") (pin "EXPAD") (pintype "passive"))
      (node (ref "Y1") (pin "2") (pinfunction "2_2") (pintype "passive"))
    )
    (net (code "71") (name "Net-(D2-A)") (class "Default")
      (node (ref "D2") (pin "1") (pinfunction "A_1") (pintype "passive"))
      (node (ref "J2") (pin "5") (pinfunction "5_5") (pintype "passive"))
      (node (ref "R5") (pin "2") (pinfunction "2_2") (pintype "passive"))
      (node (ref "TP8") (pin "1") (pinfunction "1_1") (pintype "passive"))
      (node (ref "U2") (pin "24") (pinfunction "~{RESET}_(PC1_/_dW)_24") (pintype "passive"))
    )
    (net (code "72") (name "Net-(D3-A)") (class "Default")
      (node (ref "D3") (pin "1") (pinfunction "A_1") (pintype "passive"))
      (node (ref "R11") (pin "1") (pinfunction "1_1") (pintype "passive"))
      (node (ref "TP180") (pin "1") (pinfunction "1_1") (pintype "passive"))
    )
    (net (code "73") (name "Net-(D3-K)") (class "Default")
      (node (ref "D3") (pin "2") (pinfunction "K_2") (pintype "passive"))
      (node (ref "TP179") (pin "1") (pinfunction "1_1") (pintype "passive"))
      (node (ref "U2") (pin "10") (pinfunction "PD4_(INT5_/_AIN3)_10") (pintype "passive"))
    )
    (net (code "74") (name "Net-(D4-A)") (class "Default")
      (node (ref "D4") (pin "1") (pinfunction "A_1") (pintype "passive"))
      (node (ref "R12") (pin "1") (pinfunction "1_1") (pintype "passive"))
      (node (ref "TP189") (pin "1") (pinfunction "1_1") (pintype "passive"))
    )
    (net (code "75") (name "Net-(D4-K)") (class "Default")
      (node (ref "D4") (pin "2") (pinfunction "K_2") (pintype "passive"))
      (node (ref "TP190") (pin "1") (pinfunction "1_1") (pintype "passive"))
      (node (ref "U2") (pin "11") (pinfunction "PD5_(XCK_/_AIN4_/_PCINT12)_11") (pintype "passive"))
    )
    (net (code "76") (name "Net-(F1-Pad1)") (class "Default")
      (node (ref "F1") (pin "1") (pinfunction "1_1") (pintype "passive"))
      (node (ref "J3") (pin "1") (pinfunction "1_1") (pintype "passive"))
      (node (ref "TP9") (pin "1") (pinfunction "1_1") (pintype "passive"))
    )
    (net (code "77") (name "Net-(J3-Pad2)") (class "Default")
      (node (ref "J3") (pin "2") (pinfunction "2_2") (pintype "passive"))
      (node (ref "R6") (pin "1") (pinfunction "1_1") (pintype "passive"))
      (node (ref "R8") (pin "2") (pinfunction "2_2") (pintype "passive"))
      (node (ref "TP10") (pin "1") (pinfunction "1_1") (pintype "passive"))
    )
    (net (code "78") (name "Net-(J3-Pad3)") (class "Default")
      (node (ref "J3") (pin "3") (pinfunction "3_3") (pintype "passive"))
      (node (ref "R7") (pin "1") (pinfunction "1_1") (pintype "passive"))
      (node (ref "R9") (pin "2") (pinfunction "2_2") (pintype "passive"))
      (node (ref "TP11") (pin "1") (pinfunction "1_1") (pintype "passive"))
    )
    (net (code "79") (name "Net-(J3-Pad5)") (class "Default")
      (node (ref "J3") (pin "5") (pinfunction "5_5") (pintype "passive"))
      (node (ref "L1") (pin "2") (pinfunction "2_2") (pintype "passive"))
      (node (ref "R8") (pin "1") (pinfunction "1_1") (pintype "passive"))
      (node (ref "R9") (pin "1") (pinfunction "1_1") (pintype "passive"))
      (node (ref "TP168") (pin "1") (pinfunction "1_1") (pintype "passive"))
    )
    (net (code "80") (name "Net-(U1-XTAL1)") (class "Default")
      (node (ref "R4") (pin "2") (pinfunction "2_2") (pintype "passive"))
      (node (ref "TP130") (pin "1") (pinfunction "1_1") (pintype "passive"))
      (node (ref "U1") (pin "34") (pinfunction "XTAL1_34") (pintype "input"))
      (node (ref "Y1") (pin "1") (pinfunction "1_1") (pintype "passive"))
    )
    (net (code "81") (name "Net-(U1-XTAL2)") (class "Default")
      (node (ref "R4") (pin "1") (pinfunction "1_1") (pintype "passive"))
      (node (ref "TP131") (pin "1") (pinfunction "1_1") (pintype "passive"))
      (node (ref "U1") (pin "33") (pinfunction "XTAL2_33") (pintype "output"))
      (node (ref "Y1") (pin "3") (pinfunction "3_3") (pintype "passive"))
    )
    (net (code "82") (name "Net-(U2-D+)") (class "Default")
      (node (ref "R7") (pin "2") (pinfunction "2_2") (pintype "passive"))
      (node (ref "TP170") (pin "1") (pinfunction "1_1") (pintype "passive"))
      (node (ref "U2") (pin "29") (pinfunction "D+_29") (pintype "passive"))
    )
    (net (code "83") (name "Net-(U2-D-)") (class "Default")
      (node (ref "R6") (pin "2") (pinfunction "2_2") (pintype "passive"))
      (node (ref "TP169") (pin "1") (pinfunction "1_1") (pintype "passive"))
      (node (ref "U2") (pin "30") (pinfunction "D-_30") (pintype "passive"))
    )
    (net (code "84") (name "Net-(U2-PB1_(SCLK_{slash}_PCINT1))") (class "Default")
      (node (ref "J2") (pin "3") (pinfunction "3_3") (pintype "passive"))
      (node (ref "TP6") (pin "1") (pinfunction "1_1") (pintype "passive"))
      (node (ref "U2") (pin "15") (pinfunction "PB1_(SCLK_/_PCINT1)_15") (pintype "passive"))
    )
    (net (code "85") (name "Net-(U2-PB2_(PDI_{slash}_MOSI_{slash}_PCINT2))") (class "Default")
      (node (ref "J2") (pin "4") (pinfunction "4_4") (pintype "passive"))
      (node (ref "TP7") (pin "1") (pinfunction "1_1") (pintype "passive"))
      (node (ref "U2") (pin "16") (pinfunction "PB2_(PDI_/_MOSI_/_PCINT2)_16") (pintype "passive"))
    )
    (net (code "86") (name "Net-(U2-PB3_(PDO_{slash}_MISO_{slash}_PCINT3))") (class "Default")
      (node (ref "J2") (pin "1") (pinfunction "1_1") (pintype "passive"))
      (node (ref "TP5") (pin "1") (pinfunction "1_1") (pintype "passive"))
      (node (ref "U2") (pin "17") (pinfunction "PB3_(PDO_/_MISO_/_PCINT3)_17") (pintype "passive"))
    )
    (net (code "87") (name "Net-(U2-PB4_(T1_{slash}_PCINT4))") (class "Default")
      (node (ref "J4") (pin "1") (pinfunction "1_1") (pintype "passive"))
      (node (ref "TP66") (pin "1") (pinfunction "1_1") (pintype "passive"))
      (node (ref "U2") (pin "18") (pinfunction "PB4_(T1_/_PCINT4)_18") (pintype "passive"))
    )
    (net (code "88") (name "Net-(U2-PB5_(PCINT5))") (class "Default")
      (node (ref "J4") (pin "3") (pinfunction "3_3") (pintype "passive"))
      (node (ref "TP68") (pin "1") (pinfunction "1_1") (pintype "passive"))
      (node (ref "U2") (pin "19") (pinfunction "PB5_(PCINT5)_19") (pintype "passive"))
    )
    (net (code "89") (name "Net-(U2-PB6_(PCINT6))") (class "Default")
      (node (ref "J4") (pin "2") (pinfunction "2_2") (pintype "passive"))
      (node (ref "TP67") (pin "1") (pinfunction "1_1") (pintype "passive"))
      (node (ref "U2") (pin "20") (pinfunction "PB6_(PCINT6)_20") (pintype "passive"))
    )
    (net (code "90") (name "Net-(U2-PB7_(PCINT7_{slash}_OC.0A_{slash}_OC.1C))") (class "Default")
      (node (ref "J4") (pin "4") (pinfunction "4_4") (pintype "passive"))
      (node (ref "TP69") (pin "1") (pinfunction "1_1") (pintype "passive"))
      (node (ref "U2") (pin "21") (pinfunction "PB7_(PCINT7_/_OC.0A_/_OC.1C)_21") (pintype "passive"))
    )
    (net (code "91") (name "Net-(U2-PD2_(RXD1_{slash}_AIN1_{slash}_INT2))") (class "Default")
      (node (ref "R13") (pin "1") (pinfunction "1_1") (pintype "passive"))
      (node (ref "TP174") (pin "1") (pinfunction "1_1") (pintype "passive"))
      (node (ref "U2") (pin "8") (pinfunction "PD2_(RXD1_/_AIN1_/_INT2)_8") (pintype "passive"))
    )
    (net (code "92") (name "Net-(U2-PD3_(TXD1_{slash}_INT3))") (class "Default")
      (node (ref "R14") (pin "1") (pinfunction "1_1") (pintype "passive"))
      (node (ref "TP175") (pin "1") (pinfunction "1_1") (pintype "passive"))
      (node (ref "U2") (pin "9") (pinfunction "PD3_(TXD1_/_INT3)_9") (pintype "passive"))
    )
    (net (code "93") (name "Net-(U2-PD7_(~{CTS}_{slash}_~{HWB}_{slash}_AIN6_{slash}_T0_{slash}_INT7))") (class "Default")
      (node (ref "C11") (pin "2") (pinfunction "2_2") (pintype "passive"))
      (node (ref "R15") (pin "1") (pinfunction "1_1") (pintype "passive"))
      (node (ref "TP178") (pin "1") (pinfunction "1_1") (pintype "passive"))
      (node (ref "U2") (pin "13") (pinfunction "PD7_(~{CTS}_/_~{HWB}_/_AIN6_/_T0_/_INT7)_13") (pintype "passive"))
    )
    (net (code "94") (name "Net-(U2-UCAP)") (class "Default")
      (node (ref "C6") (pin "2") (pinfunction "2_2") (pintype "passive"))
      (node (ref "TP171") (pin "1") (pinfunction "1_1") (pintype "passive"))
      (node (ref "U2") (pin "27") (pinfunction "UCAP_27") (pintype "passive"))
    )
    (net (code "95") (name "Net-(U2-UVCC)") (class "Default")
      (node (ref "C8") (pin "2") (pinfunction "2_2") (pintype "passive"))
      (node (ref "F1") (pin "2") (pinfunction "2_2") (pintype "passive"))
      (node (ref "TP167") (pin "1") (pinfunction "1_1") (pintype "passive"))
      (node (ref "U2") (pin "31") (pinfunction "UVCC_31") (pintype "passive"))
    )
    (net (code "96") (name "Net-(U2-XTAL1)") (class "Default")
      (node (ref "C7") (pin "2") (pinfunction "2_2") (pintype "passive"))
      (node (ref "R10") (pin "2") (pinfunction "2_2") (pintype "passive"))
      (node (ref "TP172") (pin "1") (pinfunction "1_1") (pintype "passive"))
      (node (ref "U2") (pin "1") (pinfunction "XTAL1_1") (pintype "passive"))
      (node (ref "Y2") (pin "2") (pinfunction "2_2") (pintype "passive"))
    )
    (net (code "97") (name "Net-(U2-XTAL2_(PC0))") (class "Default")
      (node (ref "C9") (pin "2") (pinfunction "2_2") (pintype "passive"))
      (node (ref "R10") (pin "1") (pinfunction "1_1") (pintype "passive"))
      (node (ref "TP173") (pin "1") (pinfunction "1_1") (pintype "passive"))
      (node (ref "U2") (pin "2") (pinfunction "XTAL2_(PC0)_2") (pintype "passive"))
      (node (ref "Y2") (pin "1") (pinfunction "1_1") (pintype "passive"))
    )
    (net (code "98") (name "unconnected-(U1-PA2_(AD2)-Pad76)") (class "Default")
      (node (ref "U1") (pin "76") (pinfunction "PA2_(AD2)_76") (pintype "bidirectional"))
    )
    (net (code "99") (name "unconnected-(U1-PB4_(OC2A{slash}PCINT4)-Pad23)") (class "Default")
      (node (ref "U1") (pin "23") (pinfunction "PB4_(OC2A/PCINT4)_23") (pintype "bidirectional"))
    )
    (net (code "100") (name "unconnected-(U1-PB5_(OC1A{slash}PCINT5)-Pad24)") (class "Default")
      (node (ref "U1") (pin "24") (pinfunction "PB5_(OC1A/PCINT5)_24") (pintype "bidirectional"))
    )
    (net (code "101") (name "unconnected-(U1-PB6_(OC1B{slash}PCINT6)-Pad25)") (class "Default")
      (node (ref "U1") (pin "25") (pinfunction "PB6_(OC1B/PCINT6)_25") (pintype "bidirectional"))
    )
    (net (code "102") (name "unconnected-(U1-PD4_(ICP1)-Pad47)") (class "Default")
      (node (ref "U1") (pin "47") (pinfunction "PD4_(ICP1)_47") (pintype "bidirectional"))
    )
    (net (code "103") (name "unconnected-(U1-PD5_(XCK1)-Pad48)") (class "Default")
      (node (ref "U1") (pin "48") (pinfunction "PD5_(XCK1)_48") (pintype "bidirectional"))
    )
    (net (code "104") (name "unconnected-(U1-PD6_(T1)-Pad49)") (class "Default")
      (node (ref "U1") (pin "49") (pinfunction "PD6_(T1)_49") (pintype "bidirectional"))
    )
    (net (code "105") (name "unconnected-(U1-PE2_(XCK0{slash}AIN0)-Pad4)") (class "Default")
      (node (ref "U1") (pin "4") (pinfunction "PE2_(XCK0/AIN0)_4") (pintype "bidirectional"))
    )
    (net (code "106") (name "unconnected-(U1-PE6_(T3{slash}INT6)-Pad8)") (class "Default")
      (node (ref "U1") (pin "8") (pinfunction "PE6_(T3/INT6)_8") (pintype "bidirectional"))
    )
    (net (code "107") (name "unconnected-(U1-PE7_(CLKO{slash}ICP3{slash}INT7)-Pad9)") (class "Default")
      (node (ref "U1") (pin "9") (pinfunction "PE7_(CLKO/ICP3/INT7)_9") (pintype "bidirectional"))
    )
    (net (code "108") (name "unconnected-(U1-PG3_(TOSC2)-Pad28)") (class "Default")
      (node (ref "U1") (pin "28") (pinfunction "PG3_(TOSC2)_28") (pintype "bidirectional"))
    )
    (net (code "109") (name "unconnected-(U1-PG4_(TOSC1)-Pad29)") (class "Default")
      (node (ref "U1") (pin "29") (pinfunction "PG4_(TOSC1)_29") (pintype "bidirectional"))
    )
    (net (code "110") (name "unconnected-(U1-PH2_(XCK2)-Pad14)") (class "Default")
      (node (ref "U1") (pin "14") (pinfunction "PH2_(XCK2)_14") (pintype "bidirectional"))
    )
    (net (code "111") (name "unconnected-(U1-PH6_(OC2B)-Pad18)") (class "Default")
      (node (ref "U1") (pin "18") (pinfunction "PH6_(OC2B)_18") (pintype "bidirectional"))
    )
    (net (code "112") (name "unconnected-(U1-PH7_(T4)-Pad27)") (class "Default")
      (node (ref "U1") (pin "27") (pinfunction "PH7_(T4)_27") (pintype "bidirectional"))
    )
    (net (code "113") (name "unconnected-(U1-PJ2_(XCK3{slash}PCINT11)-Pad65)") (class "Default")
      (node (ref "U1") (pin "65") (pinfunction "PJ2_(XCK3/PCINT11)_65") (pintype "bidirectional"))
    )
    (net (code "114") (name "unconnected-(U1-PJ3_(PCINT12)-Pad66)") (class "Default")
      (node (ref "U1") (pin "66") (pinfunction "PJ3_(PCINT12)_66") (pintype "bidirectional"))
    )
    (net (code "115") (name "unconnected-(U1-PJ4_(PCINT13)-Pad67)") (class "Default")
      (node (ref "U1") (pin "67") (pinfunction "PJ4_(PCINT13)_67") (pintype "bidirectional"))
    )
    (net (code "116") (name "unconnected-(U1-PJ5_(PCINT14)-Pad68)") (class "Default")
      (node (ref "U1") (pin "68") (pinfunction "PJ5_(PCINT14)_68") (pintype "bidirectional"))
    )
    (net (code "117") (name "unconnected-(U1-PJ7-Pad79)") (class "Default")
      (node (ref "U1") (pin "79") (pinfunction "PJ7_79") (pintype "bidirectional"))
    )
    (net (code "118") (name "unconnected-(U2-PB0_(~{SS}_{slash}_PCINT0)-Pad14)") (class "Default")
      (node (ref "U2") (pin "14") (pinfunction "PB0_(~{SS}_/_PCINT0)_14") (pintype "passive"))
    )
    (net (code "119") (name "unconnected-(U2-PC2_(PCINT11_{slash}_AIN2)-Pad5)") (class "Default")
      (node (ref "U2") (pin "5") (pinfunction "PC2_(PCINT11_/_AIN2)_5") (pintype "passive"))
    )
    (net (code "120") (name "unconnected-(U2-PC4_(PCINT10)-Pad26)") (class "Default")
      (node (ref "U2") (pin "26") (pinfunction "PC4_(PCINT10)_26") (pintype "passive"))
    )
    (net (code "121") (name "unconnected-(U2-PC5_(PCINT9_{slash}_OC.1B)-Pad25)") (class "Default")
      (node (ref "U2") (pin "25") (pinfunction "PC5_(PCINT9_/_OC.1B)_25") (pintype "passive"))
    )
    (net (code "122") (name "unconnected-(U2-PC6_(OC.1A_{slash}_PCINT8)-Pad23)") (class "Default")
      (node (ref "U2") (pin "23") (pinfunction "PC6_(OC.1A_/_PCINT8)_23") (pintype "passive"))
    )
    (net (code "123") (name "unconnected-(U2-PC7_(INT4_{slash}_ICP1_{slash}_CLKO)-Pad22)") (class "Default")
      (node (ref "U2") (pin "22") (pinfunction "PC7_(INT4_/_ICP1_/_CLKO)_22") (pintype "passive"))
    )
    (net (code "124") (name "unconnected-(U2-PD0_(OC.0B_{slash}_INT0)-Pad6)") (class "Default")
      (node (ref "U2") (pin "6") (pinfunction "PD0_(OC.0B_/_INT0)_6") (pintype "passive"))
    )
    (net (code "125") (name "unconnected-(U2-PD1_(AIN0_{slash}_INT1)-Pad7)") (class "Default")
      (node (ref "U2") (pin "7") (pinfunction "PD1_(AIN0_/_INT1)_7") (pintype "passive"))
    )
    (net (code "126") (name "unconnected-(U2-PD6_(~{RTS}_{slash}_AIN5_{slash}_INT6)-Pad12)") (class "Default")
      (node (ref "U2") (pin "12") (pinfunction "PD6_(~{RTS}_/_AIN5_/_INT6)_12") (pintype "passive"))
    )
  )
)
